# design.net
KiCad netlist of a schematic drawn in Altium Designer
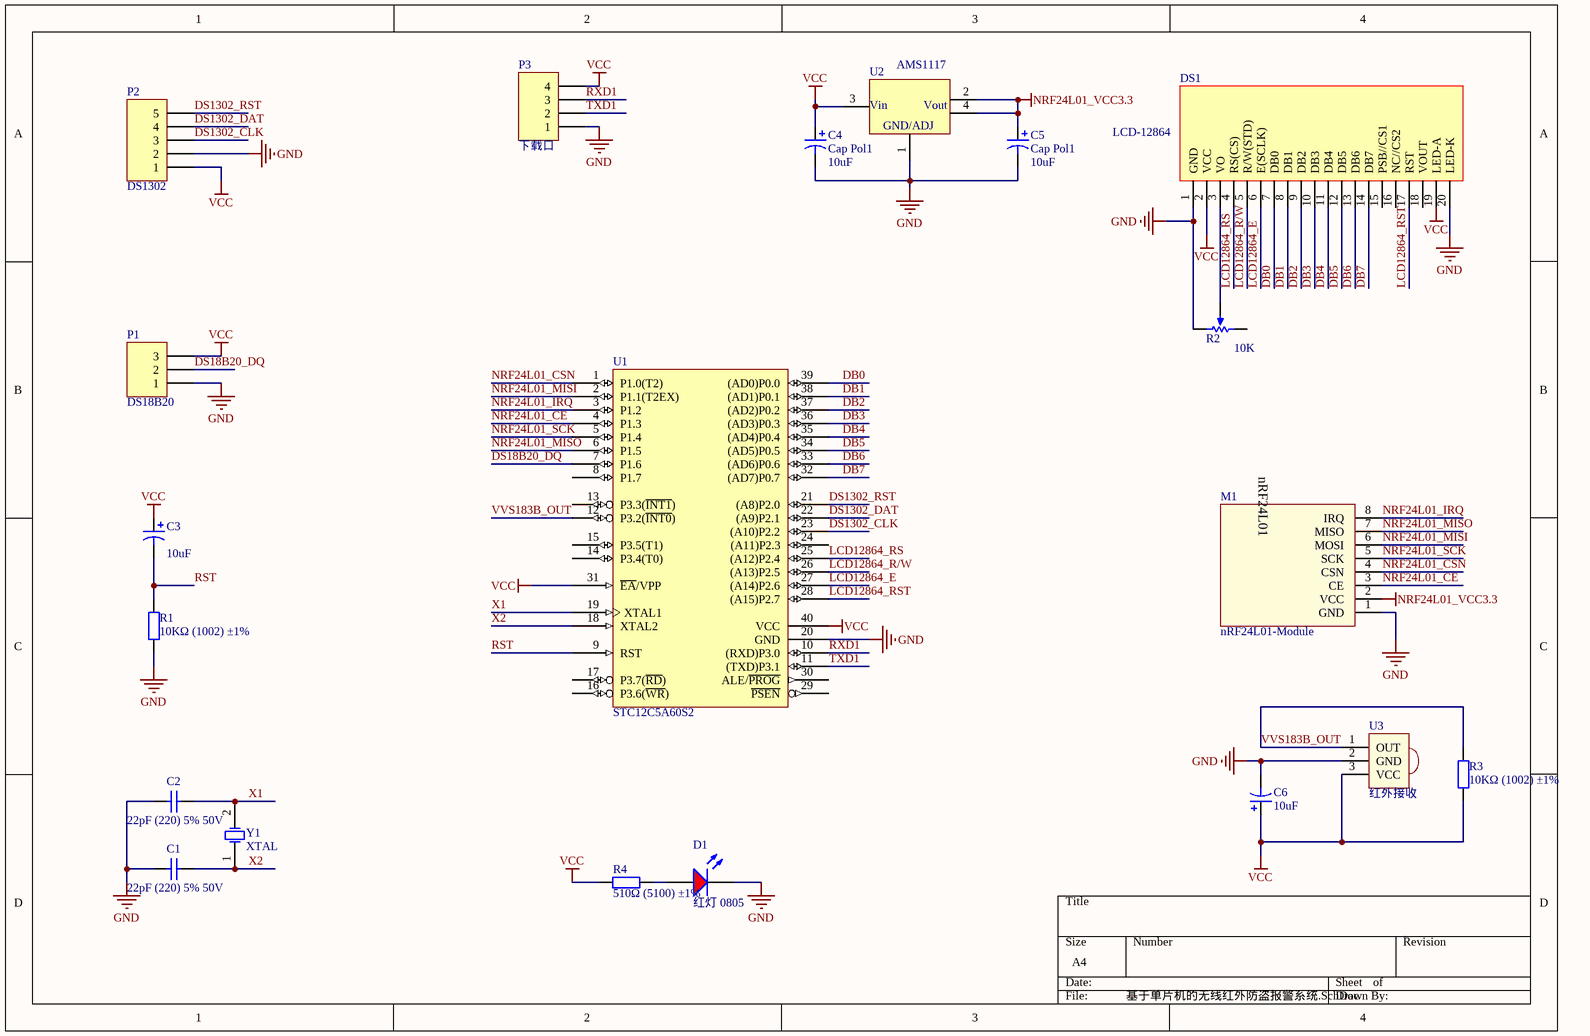
[diagram p0: 基于单片机的无线红外防盗报警系统.SchDoc]

(export (version "E")
  (design (tool "Eeschema 10.0.6"))
  (components
    (comp (ref "C1")
      (value "22pF (220) 5% 50V")
      (footprint "LC-0805_C")
      (description "贴片电容")
      (libsource (lib "Miscellaneous Devices LC") (part "0805 22pF (220) 5% 50V"))
    )
    (comp (ref "C2")
      (value "22pF (220) 5% 50V")
      (footprint "LC-0805_C")
      (description "贴片电容")
      (libsource (lib "Miscellaneous Devices LC") (part "0805 22pF (220) 5% 50V"))
    )
    (comp (ref "C3")
      (value "10uF")
      (footprint "RB.2.5/.6.3mm")
      (description "Polarized Capacitor (Radial)")
      (fields (field (name "Comment") "Cap Pol1") (field (name "PUBLISHER") "Altium Limited"))
      (libsource (lib "Miscellaneous Devices") (part "Cap Pol1"))
    )
    (comp (ref "C4")
      (value "Cap Pol1")
      (footprint "RB.2.5/.6.3mm")
      (description "Polarized Capacitor (Radial)")
      (fields (field (name "ALTIUM_VALUE") "10uF") (field (name "PUBLISHER") "Altium Limited"))
      (libsource (lib "Miscellaneous Devices") (part "Cap Pol1"))
    )
    (comp (ref "C5")
      (value "Cap Pol1")
      (footprint "RB.2.5/.6.3mm")
      (description "Polarized Capacitor (Radial)")
      (fields (field (name "ALTIUM_VALUE") "10uF") (field (name "PUBLISHER") "Altium Limited"))
      (libsource (lib "Miscellaneous Devices") (part "Cap Pol1"))
    )
    (comp (ref "C6")
      (value "10uF")
      (footprint "RB.2.5/.6.3mm")
      (description "Polarized Capacitor (Radial)")
      (fields (field (name "Comment") "Cap Pol1") (field (name "PUBLISHER") "Altium Limited"))
      (libsource (lib "Miscellaneous Devices") (part "Cap Pol1"))
    )
    (comp (ref "D1")
      (value "红灯 0805")
      (footprint "LC-0805_LED_S1")
      (description "发光二极管")
      (libsource (lib "Miscellaneous Devices LC") (part "0805 红灯"))
    )
    (comp (ref "DS1")
      (value "LCD-12864")
      (footprint "LCD-12864")
      (description "带//不带字库")
      (libsource (lib "个人") (part "LCD-12864"))
    )
    (comp (ref "M1")
      (value "nRF24L01-Module")
      (footprint "HDR2X4")
      (libsource (lib "个人") (part "nRF24L01-Module"))
    )
    (comp (ref "P1")
      (value "DS18B20")
      (footprint "HDR1X3")
      (description "Header, 3-Pin")
      (fields (field (name "PUBLISHER") "Altium Limited"))
      (libsource (lib "Miscellaneous Connectors") (part "Header 3"))
    )
    (comp (ref "P2")
      (value "DS1302")
      (footprint "HDR1X5")
      (description "Header, 5-Pin")
      (fields (field (name "PUBLISHER") "Altium Limited"))
      (libsource (lib "Miscellaneous Connectors") (part "Header 5"))
    )
    (comp (ref "P3")
      (value "下载口")
      (footprint "HDR1X4")
      (description "Header, 4-Pin")
      (fields (field (name "PUBLISHER") "Altium Limited"))
      (libsource (lib "Miscellaneous Connectors") (part "Header 4"))
    )
    (comp (ref "R1")
      (value "10KΩ (1002) ±1%")
      (footprint "LC-0805_R")
      (description "贴片电阻")
      (libsource (lib "Miscellaneous Devices LC") (part "0805 10KΩ (1002) 1%"))
    )
    (comp (ref "R2")
      (value "10K")
      (footprint "VR5")
      (description "Potentiometer")
      (fields (field (name "Comment") "Pot") (field (name "PUBLISHER") "Altium Limited"))
      (libsource (lib "Miscellaneous Devices") (part "RPot"))
    )
    (comp (ref "R3")
      (value "10KΩ (1002) ±1%")
      (footprint "LC-0805_R")
      (description "贴片电阻")
      (libsource (lib "Miscellaneous Devices LC") (part "0805 10KΩ (1002) 1%"))
    )
    (comp (ref "R4")
      (value "510Ω (5100) ±1%")
      (footprint "LC-0805_R")
      (description "贴片电阻")
      (libsource (lib "Miscellaneous Devices LC") (part "0805 510Ω (5100) 1%"))
    )
    (comp (ref "U1")
      (value "STC12C5A60S2")
      (footprint "DIP40")
      (description "8-Bit Microcontroller with 8K Flash ROM")
      (libsource (lib "Atmel Microcontroller 8051 Architecture") (part "AT89C52"))
    )
    (comp (ref "U2") (value "AMS1117") (footprint "LC-SOT-223") (libsource (lib "个人") (part "AMS1117")))
    (comp (ref "U3")
      (value "红外接收")
      (footprint "HDR1X3")
      (description "VS838")
      (libsource (lib "个人") (part "红外接收"))
    )
    (comp (ref "Y1")
      (value "XTAL")
      (footprint "R38")
      (description "Crystal Oscillator")
      (fields (field (name "PUBLISHER") "Altium Limited"))
      (libsource (lib "Miscellaneous Devices") (part "XTAL"))
    )
  )
  (nets
    (net (code "1") (name "/DB0") (class "Default")
      (node (ref "DS1") (pin "7") (pinfunction "DB0_7") (pintype "passive"))
      (node (ref "U1") (pin "39") (pinfunction "(AD0)P0.0_39") (pintype "bidirectional"))
    )
    (net (code "2") (name "/DB1") (class "Default")
      (node (ref "DS1") (pin "8") (pinfunction "DB1_8") (pintype "passive"))
      (node (ref "U1") (pin "38") (pinfunction "(AD1)P0.1_38") (pintype "bidirectional"))
    )
    (net (code "3") (name "/DB2") (class "Default")
      (node (ref "DS1") (pin "9") (pinfunction "DB2_9") (pintype "passive"))
      (node (ref "U1") (pin "37") (pinfunction "(AD2)P0.2_37") (pintype "bidirectional"))
    )
    (net (code "4") (name "/DB3") (class "Default")
      (node (ref "DS1") (pin "10") (pinfunction "DB3_10") (pintype "passive"))
      (node (ref "U1") (pin "36") (pinfunction "(AD3)P0.3_36") (pintype "bidirectional"))
    )
    (net (code "5") (name "/DB4") (class "Default")
      (node (ref "DS1") (pin "11") (pinfunction "DB4_11") (pintype "passive"))
      (node (ref "U1") (pin "35") (pinfunction "(AD4)P0.4_35") (pintype "bidirectional"))
    )
    (net (code "6") (name "/DB5") (class "Default")
      (node (ref "DS1") (pin "12") (pinfunction "DB5_12") (pintype "passive"))
      (node (ref "U1") (pin "34") (pinfunction "(AD5)P0.5_34") (pintype "bidirectional"))
    )
    (net (code "7") (name "/DB6") (class "Default")
      (node (ref "DS1") (pin "13") (pinfunction "DB6_13") (pintype "passive"))
      (node (ref "U1") (pin "33") (pinfunction "(AD6)P0.6_33") (pintype "bidirectional"))
    )
    (net (code "8") (name "/DB7") (class "Default")
      (node (ref "DS1") (pin "14") (pinfunction "DB7_14") (pintype "passive"))
      (node (ref "U1") (pin "32") (pinfunction "(AD7)P0.7_32") (pintype "bidirectional"))
    )
    (net (code "9") (name "/DS18B20_DQ") (class "Default")
      (node (ref "P1") (pin "2") (pinfunction "2_2") (pintype "passive"))
      (node (ref "U1") (pin "7") (pinfunction "P1.6_7") (pintype "bidirectional"))
    )
    (net (code "10") (name "/DS1302_CLK") (class "Default")
      (node (ref "P2") (pin "3") (pinfunction "3_3") (pintype "passive"))
      (node (ref "U1") (pin "23") (pinfunction "(A10)P2.2_23") (pintype "bidirectional"))
    )
    (net (code "11") (name "/DS1302_DAT") (class "Default")
      (node (ref "P2") (pin "4") (pinfunction "4_4") (pintype "passive"))
      (node (ref "U1") (pin "22") (pinfunction "(A9)P2.1_22") (pintype "bidirectional"))
    )
    (net (code "12") (name "/DS1302_RST") (class "Default")
      (node (ref "P2") (pin "5") (pinfunction "5_5") (pintype "passive"))
      (node (ref "U1") (pin "21") (pinfunction "(A8)P2.0_21") (pintype "bidirectional"))
    )
    (net (code "13") (name "/LCD12864_E") (class "Default")
      (node (ref "DS1") (pin "6") (pinfunction "E(SCLK)_6") (pintype "passive"))
      (node (ref "U1") (pin "27") (pinfunction "(A14)P2.6_27") (pintype "bidirectional"))
    )
    (net (code "14") (name "/LCD12864_RS") (class "Default")
      (node (ref "DS1") (pin "4") (pinfunction "RS(CS)_4") (pintype "passive"))
      (node (ref "U1") (pin "25") (pinfunction "(A12)P2.4_25") (pintype "bidirectional"))
    )
    (net (code "15") (name "/LCD12864_RST") (class "Default")
      (node (ref "DS1") (pin "17") (pinfunction "RST_17") (pintype "passive"))
      (node (ref "U1") (pin "28") (pinfunction "(A15)P2.7_28") (pintype "bidirectional"))
    )
    (net (code "16") (name "/LCD12864_R{slash}W") (class "Default")
      (node (ref "DS1") (pin "5") (pinfunction "R/W(STD)_5") (pintype "passive"))
      (node (ref "U1") (pin "26") (pinfunction "(A13)P2.5_26") (pintype "bidirectional"))
    )
    (net (code "17") (name "/NRF24L01_CE") (class "Default")
      (node (ref "M1") (pin "3") (pinfunction "CE_3") (pintype "passive"))
      (node (ref "U1") (pin "4") (pinfunction "P1.3_4") (pintype "bidirectional"))
    )
    (net (code "18") (name "/NRF24L01_CSN") (class "Default")
      (node (ref "M1") (pin "4") (pinfunction "CSN_4") (pintype "passive"))
      (node (ref "U1") (pin "1") (pinfunction "P1.0(T2)_1") (pintype "bidirectional"))
    )
    (net (code "19") (name "/NRF24L01_IRQ") (class "Default")
      (node (ref "M1") (pin "8") (pinfunction "IRQ_8") (pintype "passive"))
      (node (ref "U1") (pin "3") (pinfunction "P1.2_3") (pintype "bidirectional"))
    )
    (net (code "20") (name "/NRF24L01_MISI") (class "Default")
      (node (ref "M1") (pin "6") (pinfunction "MOSI_6") (pintype "passive"))
      (node (ref "U1") (pin "2") (pinfunction "P1.1(T2EX)_2") (pintype "bidirectional"))
    )
    (net (code "21") (name "/NRF24L01_MISO") (class "Default")
      (node (ref "M1") (pin "7") (pinfunction "MISO_7") (pintype "passive"))
      (node (ref "U1") (pin "6") (pinfunction "P1.5_6") (pintype "bidirectional"))
    )
    (net (code "22") (name "/NRF24L01_SCK") (class "Default")
      (node (ref "M1") (pin "5") (pinfunction "SCK_5") (pintype "passive"))
      (node (ref "U1") (pin "5") (pinfunction "P1.4_5") (pintype "bidirectional"))
    )
    (net (code "23") (name "/RST") (class "Default")
      (node (ref "C3") (pin "2") (pinfunction "2_2") (pintype "passive"))
      (node (ref "R1") (pin "2") (pinfunction "2_2") (pintype "passive"))
      (node (ref "U1") (pin "9") (pinfunction "RST_9") (pintype "input"))
    )
    (net (code "24") (name "/RXD1") (class "Default")
      (node (ref "P3") (pin "3") (pinfunction "3_3") (pintype "passive"))
      (node (ref "U1") (pin "10") (pinfunction "(RXD)P3.0_10") (pintype "bidirectional"))
    )
    (net (code "25") (name "/TXD1") (class "Default")
      (node (ref "P3") (pin "2") (pinfunction "2_2") (pintype "passive"))
      (node (ref "U1") (pin "11") (pinfunction "(TXD)P3.1_11") (pintype "bidirectional"))
    )
    (net (code "26") (name "/VVS183B_OUT") (class "Default")
      (node (ref "R3") (pin "2") (pinfunction "2_2") (pintype "passive"))
      (node (ref "U1") (pin "12") (pinfunction "P3.2(~{INT0})_12") (pintype "bidirectional"))
      (node (ref "U3") (pin "1") (pinfunction "OUT_1") (pintype "passive"))
    )
    (net (code "27") (name "/X1") (class "Default")
      (node (ref "C2") (pin "2") (pinfunction "2_2") (pintype "passive"))
      (node (ref "U1") (pin "19") (pinfunction "XTAL1_19") (pintype "input"))
      (node (ref "Y1") (pin "2") (pinfunction "OSC2_2") (pintype "passive"))
    )
    (net (code "28") (name "/X2") (class "Default")
      (node (ref "C1") (pin "2") (pinfunction "2_2") (pintype "passive"))
      (node (ref "U1") (pin "18") (pinfunction "XTAL2_18") (pintype "input"))
      (node (ref "Y1") (pin "1") (pinfunction "OSC1_1") (pintype "passive"))
    )
    (net (code "29") (name "GND") (class "Default")
      (node (ref "C1") (pin "1") (pinfunction "1_1") (pintype "passive"))
      (node (ref "C2") (pin "1") (pinfunction "1_1") (pintype "passive"))
      (node (ref "C4") (pin "2") (pinfunction "2_2") (pintype "passive"))
      (node (ref "C5") (pin "2") (pinfunction "2_2") (pintype "passive"))
      (node (ref "C6") (pin "2") (pinfunction "2_2") (pintype "passive"))
      (node (ref "D1") (pin "K") (pinfunction "K_K") (pintype "passive"))
      (node (ref "DS1") (pin "1") (pinfunction "GND_1") (pintype "passive"))
      (node (ref "DS1") (pin "20") (pinfunction "LED-K_20") (pintype "passive"))
      (node (ref "M1") (pin "1") (pinfunction "GND_1") (pintype "passive"))
      (node (ref "P1") (pin "1") (pinfunction "1_1") (pintype "passive"))
      (node (ref "P2") (pin "2") (pinfunction "2_2") (pintype "passive"))
      (node (ref "P3") (pin "1") (pinfunction "1_1") (pintype "passive"))
      (node (ref "R1") (pin "1") (pinfunction "1_1") (pintype "passive"))
      (node (ref "R2") (pin "2") (pinfunction "BOT_2") (pintype "passive"))
      (node (ref "U1") (pin "20") (pinfunction "GND_20") (pintype "power_in"))
      (node (ref "U2") (pin "1") (pintype "passive"))
      (node (ref "U3") (pin "2") (pinfunction "GND_2") (pintype "passive"))
    )
    (net (code "30") (name "NRF24L01_VCC3.3") (class "Default")
      (node (ref "C5") (pin "1") (pinfunction "1_1") (pintype "passive"))
      (node (ref "M1") (pin "2") (pinfunction "VCC_2") (pintype "passive"))
      (node (ref "U2") (pin "2") (pintype "passive"))
      (node (ref "U2") (pin "4") (pintype "passive"))
    )
    (net (code "31") (name "Net-(D1-PadA)") (class "Default")
      (node (ref "D1") (pin "A") (pinfunction "A_A") (pintype "passive"))
      (node (ref "R4") (pin "2") (pinfunction "2_2") (pintype "passive"))
    )
    (net (code "32") (name "Net-(DS1-VO)") (class "Default")
      (node (ref "DS1") (pin "3") (pinfunction "VO_3") (pintype "passive"))
      (node (ref "R2") (pin "3") (pinfunction "TAP_3") (pintype "passive"))
    )
    (net (code "33") (name "VCC") (class "Default")
      (node (ref "C3") (pin "1") (pinfunction "1_1") (pintype "passive"))
      (node (ref "C4") (pin "1") (pinfunction "1_1") (pintype "passive"))
      (node (ref "C6") (pin "1") (pinfunction "1_1") (pintype "passive"))
      (node (ref "DS1") (pin "19") (pinfunction "LED-A_19") (pintype "passive"))
      (node (ref "DS1") (pin "2") (pinfunction "VCC_2") (pintype "passive"))
      (node (ref "P1") (pin "3") (pinfunction "3_3") (pintype "passive"))
      (node (ref "P2") (pin "1") (pinfunction "1_1") (pintype "passive"))
      (node (ref "P3") (pin "4") (pinfunction "4_4") (pintype "passive"))
      (node (ref "R3") (pin "1") (pinfunction "1_1") (pintype "passive"))
      (node (ref "R4") (pin "1") (pinfunction "1_1") (pintype "passive"))
      (node (ref "U1") (pin "31") (pinfunction "~{EA}/VPP_31") (pintype "input"))
      (node (ref "U1") (pin "40") (pinfunction "VCC_40") (pintype "power_in"))
      (node (ref "U2") (pin "3") (pintype "passive"))
      (node (ref "U3") (pin "3") (pinfunction "VCC_3") (pintype "passive"))
    )
    (net (code "34") (name "unconnected-(DS1-NC{slash}{slash}CS2-Pad16)") (class "Default")
      (node (ref "DS1") (pin "16") (pinfunction "NC//CS2_16") (pintype "passive"))
    )
    (net (code "35") (name "unconnected-(DS1-PSB{slash}{slash}CS1-Pad15)") (class "Default")
      (node (ref "DS1") (pin "15") (pinfunction "PSB//CS1_15") (pintype "passive"))
    )
    (net (code "36") (name "unconnected-(DS1-VOUT-Pad18)") (class "Default")
      (node (ref "DS1") (pin "18") (pinfunction "VOUT_18") (pintype "passive"))
    )
    (net (code "37") (name "unconnected-(R2-TOP-Pad1)") (class "Default")
      (node (ref "R2") (pin "1") (pinfunction "TOP_1") (pintype "passive"))
    )
    (net (code "38") (name "unconnected-(U1-(A11)P2.3-Pad24)") (class "Default")
      (node (ref "U1") (pin "24") (pinfunction "(A11)P2.3_24") (pintype "bidirectional"))
    )
    (net (code "39") (name "unconnected-(U1-ALE{slash}~{PROG}-Pad30)") (class "Default")
      (node (ref "U1") (pin "30") (pinfunction "ALE/~{PROG}_30") (pintype "output"))
    )
    (net (code "40") (name "unconnected-(U1-P1.7-Pad8)") (class "Default")
      (node (ref "U1") (pin "8") (pinfunction "P1.7_8") (pintype "bidirectional"))
    )
    (net (code "41") (name "unconnected-(U1-P3.3(~{INT1})-Pad13)") (class "Default")
      (node (ref "U1") (pin "13") (pinfunction "P3.3(~{INT1})_13") (pintype "bidirectional"))
    )
    (net (code "42") (name "unconnected-(U1-P3.4(T0)-Pad14)") (class "Default")
      (node (ref "U1") (pin "14") (pinfunction "P3.4(T0)_14") (pintype "bidirectional"))
    )
    (net (code "43") (name "unconnected-(U1-P3.5(T1)-Pad15)") (class "Default")
      (node (ref "U1") (pin "15") (pinfunction "P3.5(T1)_15") (pintype "bidirectional"))
    )
    (net (code "44") (name "unconnected-(U1-P3.6(~{WR})-Pad16)") (class "Default")
      (node (ref "U1") (pin "16") (pinfunction "P3.6(~{WR})_16") (pintype "bidirectional"))
    )
    (net (code "45") (name "unconnected-(U1-P3.7(~{RD})-Pad17)") (class "Default")
      (node (ref "U1") (pin "17") (pinfunction "P3.7(~{RD})_17") (pintype "bidirectional"))
    )
    (net (code "46") (name "unconnected-(U1-~{PSEN}-Pad29)") (class "Default")
      (node (ref "U1") (pin "29") (pinfunction "~{PSEN}_29") (pintype "output"))
    )
  )
)
